# AMEPD_Port.net
KiCad netlist of a schematic drawn in Altium Designer
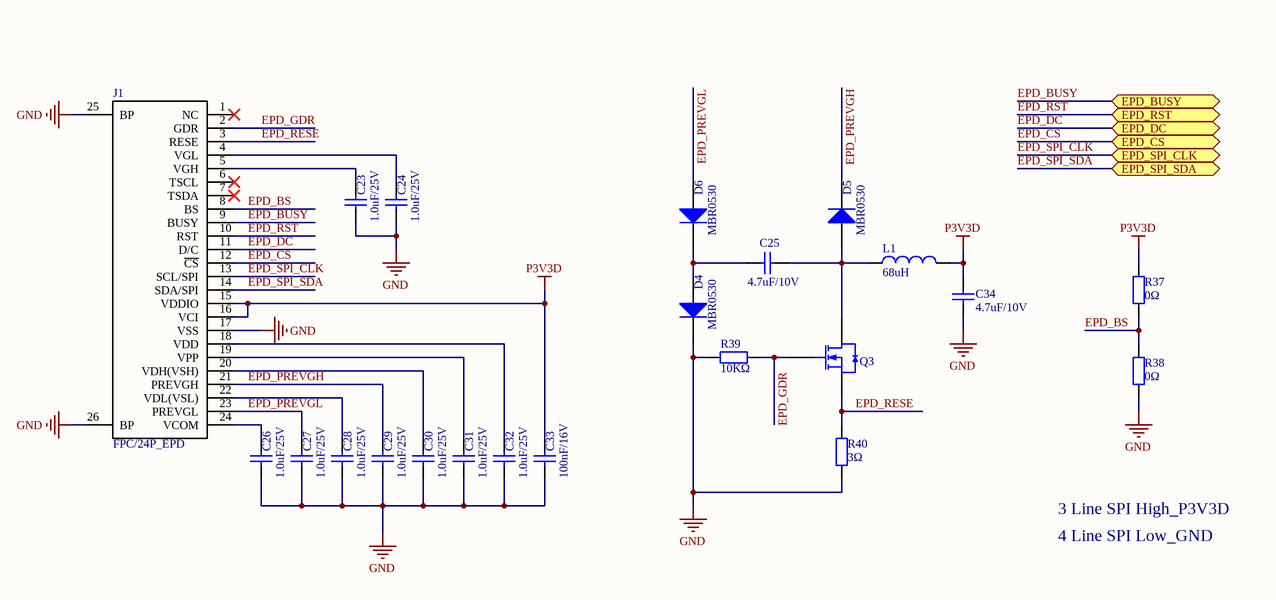
[diagram p0: AMEPD_Port.SchDoc]

(export (version "E")
  (design (tool "Eeschema 10.0.6"))
  (components
    (comp (ref "C23")
      (value "1.0uF/25V")
      (footprint "0402_C")
      (description "贴片电容")
      (libsource (lib "Miscellaneous Devices LC") (part "0402 1.0uF (105) 10% 25V"))
    )
    (comp (ref "C24")
      (value "1.0uF/25V")
      (footprint "0402_C")
      (description "贴片电容")
      (libsource (lib "Miscellaneous Devices LC") (part "0402 1.0uF (105) 10% 25V"))
    )
    (comp (ref "C25")
      (value "4.7uF/10V")
      (footprint "0402_C")
      (description "贴片电容")
      (libsource (lib "Miscellaneous Devices LC") (part "0402 4.7uF (475) 20% 10V"))
    )
    (comp (ref "C26")
      (value "1.0uF/25V")
      (footprint "0402_C")
      (description "贴片电容")
      (libsource (lib "Miscellaneous Devices LC") (part "0402 1.0uF (105) 10% 25V"))
    )
    (comp (ref "C27")
      (value "1.0uF/25V")
      (footprint "0402_C")
      (description "贴片电容")
      (libsource (lib "Miscellaneous Devices LC") (part "0402 1.0uF (105) 10% 25V"))
    )
    (comp (ref "C28")
      (value "1.0uF/25V")
      (footprint "0402_C")
      (description "贴片电容")
      (libsource (lib "Miscellaneous Devices LC") (part "0402 1.0uF (105) 10% 25V"))
    )
    (comp (ref "C29")
      (value "1.0uF/25V")
      (footprint "0402_C")
      (description "贴片电容")
      (libsource (lib "Miscellaneous Devices LC") (part "0402 1.0uF (105) 10% 25V"))
    )
    (comp (ref "C30")
      (value "1.0uF/25V")
      (footprint "0402_C")
      (description "贴片电容")
      (libsource (lib "Miscellaneous Devices LC") (part "0402 1.0uF (105) 10% 25V"))
    )
    (comp (ref "C31")
      (value "1.0uF/25V")
      (footprint "0402_C")
      (description "贴片电容")
      (libsource (lib "Miscellaneous Devices LC") (part "0402 1.0uF (105) 10% 25V"))
    )
    (comp (ref "C32")
      (value "1.0uF/25V")
      (footprint "0402_C")
      (description "贴片电容")
      (libsource (lib "Miscellaneous Devices LC") (part "0402 1.0uF (105) 10% 25V"))
    )
    (comp (ref "C33")
      (value "100nF/16V")
      (footprint "0402_C")
      (description "贴片电容")
      (libsource (lib "Miscellaneous Devices LC") (part "0402 100nF (104) 10% 16V"))
    )
    (comp (ref "C34")
      (value "4.7uF/10V")
      (footprint "0402_C")
      (description "贴片电容")
      (libsource (lib "Miscellaneous Devices LC") (part "0402 4.7uF (475) 20% 10V"))
    )
    (comp (ref "D4")
      (value "MBR0530")
      (footprint "SOD-123")
      (description "肖特基二极管")
      (libsource (lib "Miscellaneous Devices LC") (part "SOD-123 B5819W  SL"))
    )
    (comp (ref "D5")
      (value "MBR0530")
      (footprint "SOD-123")
      (description "肖特基二极管")
      (libsource (lib "Miscellaneous Devices LC") (part "SOD-123 B5819W  SL"))
    )
    (comp (ref "D6")
      (value "MBR0530")
      (footprint "SOD-123")
      (description "肖特基二极管")
      (libsource (lib "Miscellaneous Devices LC") (part "SOD-123 B5819W  SL"))
    )
    (comp (ref "J1")
      (value "FPC/24P_EPD")
      (footprint "FPC/24P_EPD")
      (description "Active Matrix Electrophoretic Display (AMEPD)")
      (libsource (lib "Connectors") (part "FPC/24P_EPD"))
    )
    (comp (ref "L1")
      (value "68uH")
      (footprint "LSMD4X4")
      (description "Inductor")
      (libsource (lib "Discrete") (part "L"))
    )
    (comp (ref "Q3")
      (value "AO3400A N道沟 X0YV1T SOT-23")
      (footprint "SOT-23-3L")
      (description "MOS(场效应管)")
      (libsource (lib "Miscellaneous Devices LC") (part "AO3400A N道沟 X0YV1T SOT-23"))
    )
    (comp (ref "R37")
      (value "0Ω")
      (footprint "0402_R")
      (description "贴片电阻")
      (libsource (lib "Miscellaneous Devices LC") (part "0402 0Ω (0R0) 1%"))
    )
    (comp (ref "R38")
      (value "0Ω")
      (footprint "0402_R")
      (description "贴片电阻")
      (libsource (lib "Miscellaneous Devices LC") (part "0402 0Ω (0R0) 1%"))
    )
    (comp (ref "R39")
      (value "10KΩ")
      (footprint "0402_R")
      (description "贴片电阻")
      (libsource (lib "Miscellaneous Devices LC") (part "0402 10KΩ (1002) 1%"))
    )
    (comp (ref "R40")
      (value "3Ω")
      (footprint "0402_R")
      (description "贴片电阻")
      (libsource (lib "Miscellaneous Devices LC") (part "0402 33Ω (33R0) 1%"))
    )
  )
  (nets
    (net (code "1") (name "/EPD_BS") (class "Default")
      (node (ref "J1") (pin "8") (pinfunction "BS_8") (pintype "passive"))
      (node (ref "R37") (pin "1") (pinfunction "1_1") (pintype "passive"))
      (node (ref "R38") (pin "2") (pinfunction "2_2") (pintype "passive"))
    )
    (net (code "2") (name "/EPD_BUSY") (class "Default")
      (node (ref "J1") (pin "9") (pinfunction "BUSY_9") (pintype "passive"))
    )
    (net (code "3") (name "/EPD_CS") (class "Default")
      (node (ref "J1") (pin "12") (pinfunction "~{CS}_12") (pintype "passive"))
    )
    (net (code "4") (name "/EPD_DC") (class "Default")
      (node (ref "J1") (pin "11") (pinfunction "D/C_11") (pintype "passive"))
    )
    (net (code "5") (name "/EPD_GDR") (class "Default")
      (node (ref "J1") (pin "2") (pinfunction "GDR_2") (pintype "passive"))
      (node (ref "Q3") (pin "1") (pinfunction "G_1") (pintype "passive"))
      (node (ref "R39") (pin "2") (pinfunction "2_2") (pintype "passive"))
    )
    (net (code "6") (name "/EPD_PREVGH") (class "Default")
      (node (ref "C29") (pin "2") (pinfunction "2_2") (pintype "passive"))
      (node (ref "D5") (pin "2") (pinfunction "K_2") (pintype "passive"))
      (node (ref "J1") (pin "21") (pinfunction "PREVGH_21") (pintype "passive"))
    )
    (net (code "7") (name "/EPD_PREVGL") (class "Default")
      (node (ref "C27") (pin "2") (pinfunction "2_2") (pintype "passive"))
      (node (ref "D6") (pin "1") (pinfunction "A_1") (pintype "passive"))
      (node (ref "J1") (pin "23") (pinfunction "PREVGL_23") (pintype "passive"))
    )
    (net (code "8") (name "/EPD_RESE") (class "Default")
      (node (ref "J1") (pin "3") (pinfunction "RESE_3") (pintype "passive"))
      (node (ref "Q3") (pin "2") (pinfunction "S_2") (pintype "passive"))
      (node (ref "R40") (pin "2") (pinfunction "2_2") (pintype "passive"))
    )
    (net (code "9") (name "/EPD_RST") (class "Default")
      (node (ref "J1") (pin "10") (pinfunction "RST_10") (pintype "passive"))
    )
    (net (code "10") (name "/EPD_SPI_CLK") (class "Default")
      (node (ref "J1") (pin "13") (pinfunction "SCL/SPI_13") (pintype "passive"))
    )
    (net (code "11") (name "/EPD_SPI_SDA") (class "Default")
      (node (ref "J1") (pin "14") (pinfunction "SDA/SPI_14") (pintype "passive"))
    )
    (net (code "12") (name "GND") (class "Default")
      (node (ref "C23") (pin "1") (pinfunction "1_1") (pintype "passive"))
      (node (ref "C24") (pin "1") (pinfunction "1_1") (pintype "passive"))
      (node (ref "C26") (pin "1") (pinfunction "1_1") (pintype "passive"))
      (node (ref "C27") (pin "1") (pinfunction "1_1") (pintype "passive"))
      (node (ref "C28") (pin "1") (pinfunction "1_1") (pintype "passive"))
      (node (ref "C29") (pin "1") (pinfunction "1_1") (pintype "passive"))
      (node (ref "C30") (pin "1") (pinfunction "1_1") (pintype "passive"))
      (node (ref "C31") (pin "1") (pinfunction "1_1") (pintype "passive"))
      (node (ref "C32") (pin "1") (pinfunction "1_1") (pintype "passive"))
      (node (ref "C33") (pin "2") (pinfunction "2_2") (pintype "passive"))
      (node (ref "C34") (pin "1") (pinfunction "1_1") (pintype "passive"))
      (node (ref "D4") (pin "2") (pinfunction "K_2") (pintype "passive"))
      (node (ref "J1") (pin "17") (pinfunction "VSS_17") (pintype "passive"))
      (node (ref "J1") (pin "25") (pinfunction "BP_25") (pintype "passive"))
      (node (ref "J1") (pin "26") (pinfunction "BP_26") (pintype "passive"))
      (node (ref "R38") (pin "1") (pinfunction "1_1") (pintype "passive"))
      (node (ref "R39") (pin "1") (pinfunction "1_1") (pintype "passive"))
      (node (ref "R40") (pin "1") (pinfunction "1_1") (pintype "passive"))
    )
    (net (code "13") (name "Net-(D4-A)") (class "Default")
      (node (ref "C25") (pin "1") (pinfunction "1_1") (pintype "passive"))
      (node (ref "D4") (pin "1") (pinfunction "A_1") (pintype "passive"))
      (node (ref "D6") (pin "2") (pinfunction "K_2") (pintype "passive"))
    )
    (net (code "14") (name "Net-(D5-A)") (class "Default")
      (node (ref "C25") (pin "2") (pinfunction "2_2") (pintype "passive"))
      (node (ref "D5") (pin "1") (pinfunction "A_1") (pintype "passive"))
      (node (ref "L1") (pin "1") (pinfunction "1_1") (pintype "passive"))
      (node (ref "Q3") (pin "3") (pinfunction "D_3") (pintype "passive"))
    )
    (net (code "15") (name "Net-(J1-VCOM)") (class "Default")
      (node (ref "C26") (pin "2") (pinfunction "2_2") (pintype "passive"))
      (node (ref "J1") (pin "24") (pinfunction "VCOM_24") (pintype "passive"))
    )
    (net (code "16") (name "Net-(J1-VDD)") (class "Default")
      (node (ref "C32") (pin "2") (pinfunction "2_2") (pintype "passive"))
      (node (ref "J1") (pin "18") (pinfunction "VDD_18") (pintype "passive"))
    )
    (net (code "17") (name "Net-(J1-VDH(VSH))") (class "Default")
      (node (ref "C30") (pin "2") (pinfunction "2_2") (pintype "passive"))
      (node (ref "J1") (pin "20") (pinfunction "VDH(VSH)_20") (pintype "passive"))
    )
    (net (code "18") (name "Net-(J1-VDL(VSL))") (class "Default")
      (node (ref "C28") (pin "2") (pinfunction "2_2") (pintype "passive"))
      (node (ref "J1") (pin "22") (pinfunction "VDL(VSL)_22") (pintype "passive"))
    )
    (net (code "19") (name "Net-(J1-VGH)") (class "Default")
      (node (ref "C23") (pin "2") (pinfunction "2_2") (pintype "passive"))
      (node (ref "J1") (pin "5") (pinfunction "VGH_5") (pintype "passive"))
    )
    (net (code "20") (name "Net-(J1-VGL)") (class "Default")
      (node (ref "C24") (pin "2") (pinfunction "2_2") (pintype "passive"))
      (node (ref "J1") (pin "4") (pinfunction "VGL_4") (pintype "passive"))
    )
    (net (code "21") (name "Net-(J1-VPP)") (class "Default")
      (node (ref "C31") (pin "2") (pinfunction "2_2") (pintype "passive"))
      (node (ref "J1") (pin "19") (pinfunction "VPP_19") (pintype "passive"))
    )
    (net (code "22") (name "P3V3D") (class "Default")
      (node (ref "C33") (pin "1") (pinfunction "1_1") (pintype "passive"))
      (node (ref "C34") (pin "2") (pinfunction "2_2") (pintype "passive"))
      (node (ref "J1") (pin "15") (pinfunction "VDDIO_15") (pintype "passive"))
      (node (ref "J1") (pin "16") (pinfunction "VCI_16") (pintype "passive"))
      (node (ref "L1") (pin "2") (pinfunction "2_2") (pintype "passive"))
      (node (ref "R37") (pin "2") (pinfunction "2_2") (pintype "passive"))
    )
    (net (code "23") (name "unconnected-(J1-NC-Pad1)") (class "Default")
      (node (ref "J1") (pin "1") (pinfunction "NC_1") (pintype "passive+no_connect"))
    )
    (net (code "24") (name "unconnected-(J1-TSCL-Pad6)") (class "Default")
      (node (ref "J1") (pin "6") (pinfunction "TSCL_6") (pintype "passive+no_connect"))
    )
    (net (code "25") (name "unconnected-(J1-TSDA-Pad7)") (class "Default")
      (node (ref "J1") (pin "7") (pinfunction "TSDA_7") (pintype "passive+no_connect"))
    )
  )
)
